# light.net
KiCad netlist of a schematic drawn in EAGLE
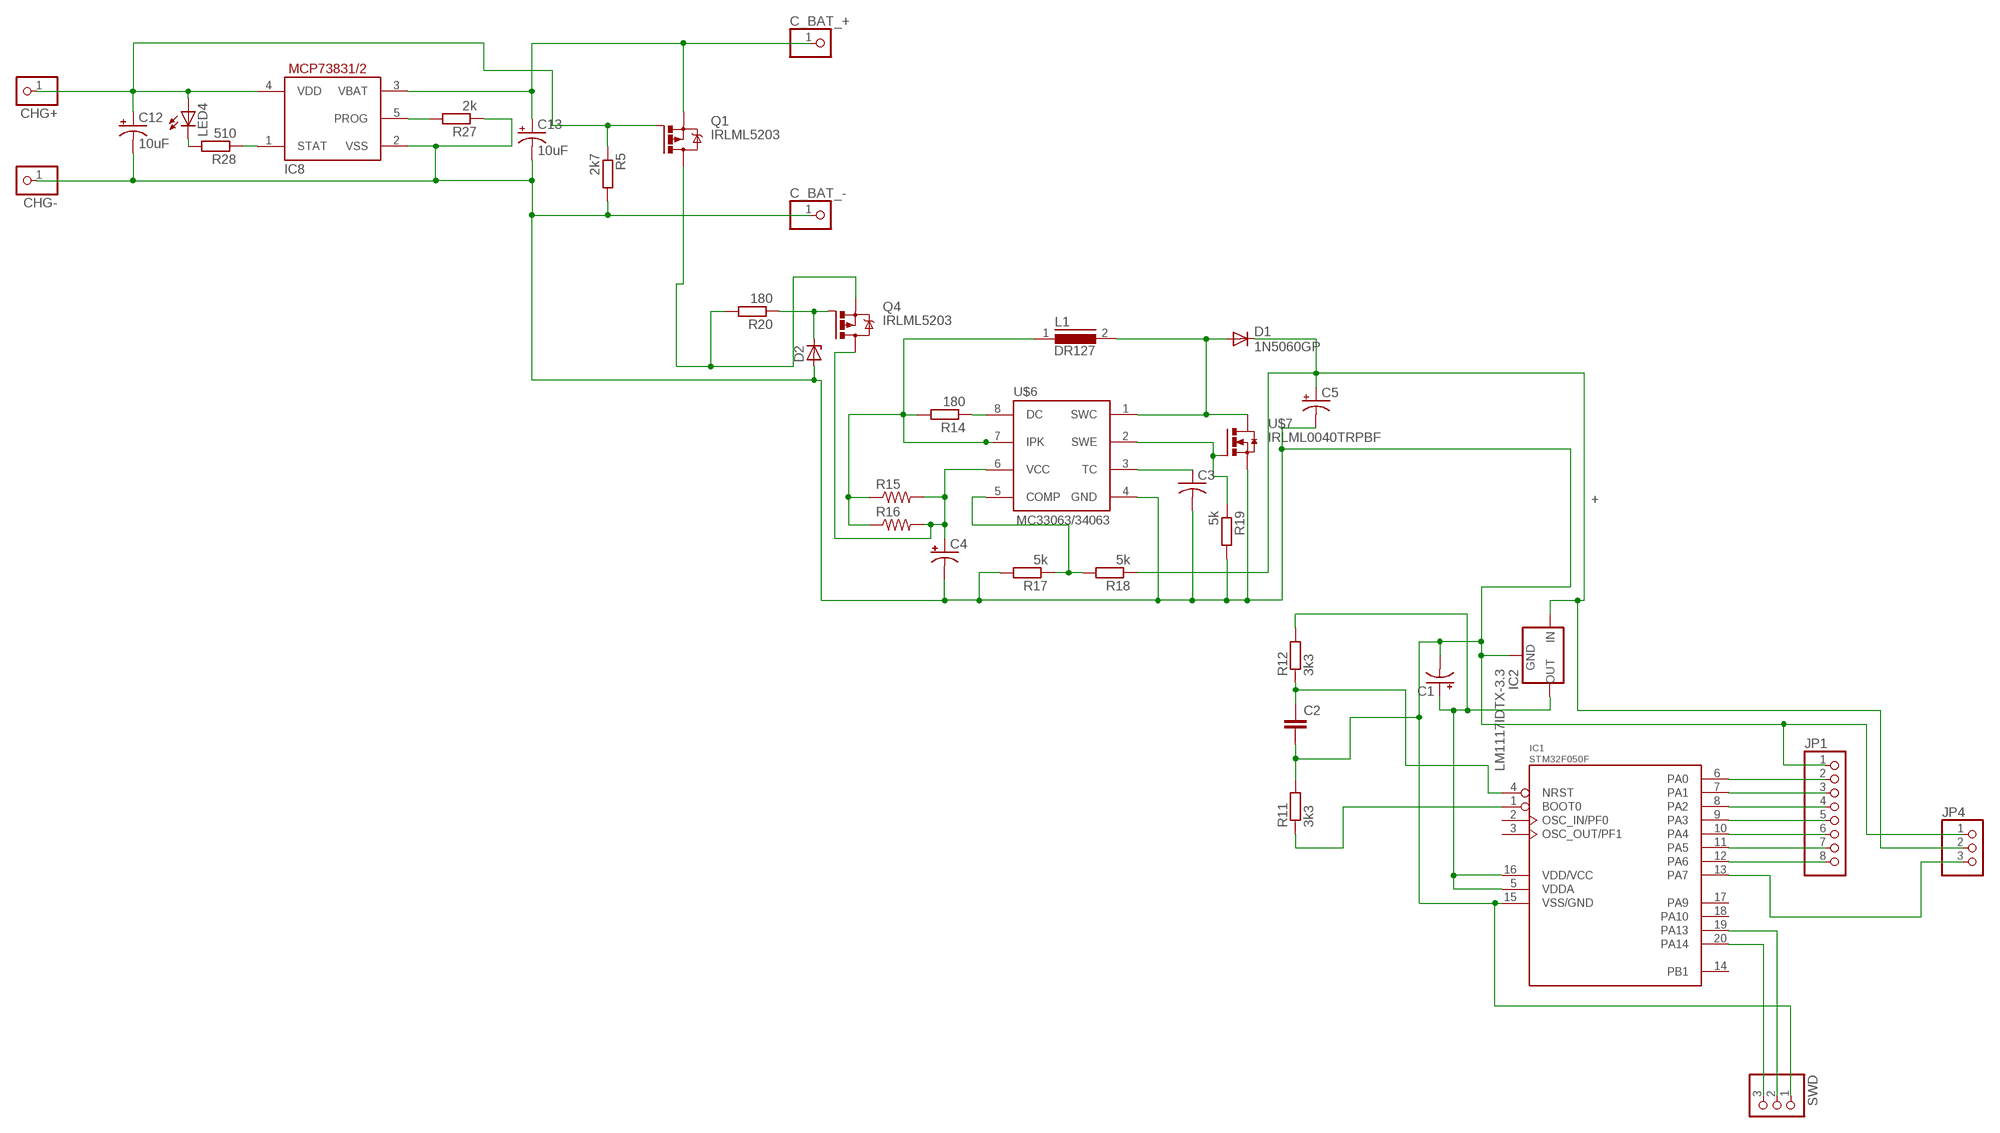
[diagram p0: schematic, sheet 1]

(export (version "E")
  (design (tool "Eeschema 10.0.6"))
  (components
    (comp (ref "C1")
      (value "CPOL-USSMCD")
      (footprint "eagle-import:SMC_D")
      (libsource (lib "eagle-import") (part "CPOL-USSMCD"))
    )
    (comp (ref "C2")
      (value "C-EUC1206")
      (footprint "eagle-import:C1206")
      (libsource (lib "eagle-import") (part "C-EUC1206"))
    )
    (comp (ref "C3")
      (value "C-US050-024X044")
      (footprint "eagle-import:C050-024X044")
      (libsource (lib "eagle-import") (part "C-US050-024X044"))
    )
    (comp (ref "C4")
      (value "CPOL-USE5-8.5")
      (footprint "eagle-import:E5-8,5")
      (libsource (lib "eagle-import") (part "CPOL-USE5-8.5"))
    )
    (comp (ref "C5")
      (value "CPOL-USE5-8.5")
      (footprint "eagle-import:E5-8,5")
      (libsource (lib "eagle-import") (part "CPOL-USE5-8.5"))
    )
    (comp (ref "C12")
      (value "10uF")
      (footprint "eagle-import:SMC_D")
      (libsource (lib "eagle-import") (part "CPOL-USSMCD"))
    )
    (comp (ref "C13")
      (value "10uF")
      (footprint "eagle-import:SMC_D")
      (libsource (lib "eagle-import") (part "CPOL-USSMCD"))
    )
    (comp (ref "CHG+")
      (value "PINHD-1X1")
      (footprint "eagle-import:1X01")
      (libsource (lib "eagle-import") (part "PINHD-1X1"))
    )
    (comp (ref "CHG-")
      (value "PINHD-1X1")
      (footprint "eagle-import:1X01")
      (libsource (lib "eagle-import") (part "PINHD-1X1"))
    )
    (comp (ref "C_BAT_+")
      (value "PINHD-1X1")
      (footprint "eagle-import:1X01")
      (libsource (lib "eagle-import") (part "PINHD-1X1"))
    )
    (comp (ref "C_BAT_-")
      (value "PINHD-1X1")
      (footprint "eagle-import:1X01")
      (libsource (lib "eagle-import") (part "PINHD-1X1"))
    )
    (comp (ref "D1")
      (value "1N5060GP")
      (footprint "eagle-import:DO15-12")
      (libsource (lib "eagle-import") (part "1N5060GP"))
    )
    (comp (ref "D2")
      (value "ZENER-DIODESOD80C")
      (footprint "eagle-import:SOD80C")
      (libsource (lib "eagle-import") (part "ZENER-DIODESOD80C"))
    )
    (comp (ref "IC1")
      (value "STM32F050F")
      (footprint "eagle-import:TSSOP20")
      (libsource (lib "eagle-import") (part "STM32F050F"))
    )
    (comp (ref "IC2")
      (value "LM1117IDTX-3.3")
      (footprint "eagle-import:TO252")
      (libsource (lib "eagle-import") (part "LM1117IDTX-3.3"))
    )
    (comp (ref "IC8")
      (value "MCP73831/OT")
      (footprint "eagle-import:SOT23-5L")
      (libsource (lib "eagle-import") (part "MCP73831/OT"))
    )
    (comp (ref "JP1")
      (value "PINHD-1X8")
      (footprint "eagle-import:1X08")
      (libsource (lib "eagle-import") (part "PINHD-1X8"))
    )
    (comp (ref "JP4")
      (value "PINHD-1X3")
      (footprint "eagle-import:1X03")
      (libsource (lib "eagle-import") (part "pinhead_PINHD-1X3"))
    )
    (comp (ref "L1")
      (value "DR127")
      (footprint "eagle-import:DR127")
      (libsource (lib "eagle-import") (part "DR127"))
    )
    (comp (ref "LED4")
      (value "LED")
      (footprint "eagle-import:SMARTLED-TTW")
      (libsource (lib "eagle-import") (part "LED"))
    )
    (comp (ref "Q1")
      (value "IRLML5203")
      (footprint "eagle-import:MICRO3")
      (libsource (lib "eagle-import") (part "IRLML5203"))
    )
    (comp (ref "Q4")
      (value "IRLML5203")
      (footprint "eagle-import:MICRO3")
      (libsource (lib "eagle-import") (part "IRLML5203"))
    )
    (comp (ref "R5")
      (value "2k7")
      (footprint "eagle-import:M1206")
      (libsource (lib "eagle-import") (part "R-EU_M1206"))
    )
    (comp (ref "R11")
      (value "3k3")
      (footprint "eagle-import:M1206")
      (libsource (lib "eagle-import") (part "R-EU_M1206"))
    )
    (comp (ref "R12")
      (value "3k3")
      (footprint "eagle-import:M1206")
      (libsource (lib "eagle-import") (part "R-EU_M1206"))
    )
    (comp (ref "R14")
      (value "180")
      (footprint "eagle-import:M1206")
      (libsource (lib "eagle-import") (part "R-EU_M1206"))
    )
    (comp (ref "R15")
      (value "R-US_0207/12")
      (footprint "eagle-import:0207_12")
      (libsource (lib "eagle-import") (part "R-US_0207/12"))
    )
    (comp (ref "R16")
      (value "R-US_0207/12")
      (footprint "eagle-import:0207_12")
      (libsource (lib "eagle-import") (part "R-US_0207/12"))
    )
    (comp (ref "R17")
      (value "5k")
      (footprint "eagle-import:M1206")
      (libsource (lib "eagle-import") (part "R-EU_M1206"))
    )
    (comp (ref "R18")
      (value "5k")
      (footprint "eagle-import:M1206")
      (libsource (lib "eagle-import") (part "R-EU_M1206"))
    )
    (comp (ref "R19")
      (value "5k")
      (footprint "eagle-import:M1206")
      (libsource (lib "eagle-import") (part "R-EU_M1206"))
    )
    (comp (ref "R20")
      (value "180")
      (footprint "eagle-import:M1206")
      (libsource (lib "eagle-import") (part "R-EU_M1206"))
    )
    (comp (ref "R27")
      (value "2k")
      (footprint "eagle-import:M1206")
      (libsource (lib "eagle-import") (part "R-EU_M1206"))
    )
    (comp (ref "R28")
      (value "510")
      (footprint "eagle-import:M1206")
      (libsource (lib "eagle-import") (part "R-EU_M1206"))
    )
    (comp (ref "SWD")
      (value "PINHD-1X3")
      (footprint "eagle-import:1X03")
      (libsource (lib "eagle-import") (part "PINHD-1X3"))
    )
    (comp (ref "U$6")
      (value "MC33063/MC34063D")
      (footprint "eagle-import:SO08")
      (libsource (lib "eagle-import") (part "MC33063/MC34063D"))
    )
    (comp (ref "U$7")
      (value "IRLML0040TRPBF")
      (footprint "eagle-import:MICRO3")
      (libsource (lib "eagle-import") (part "IRLML0040TRPBF"))
    )
  )
  (nets
    (net (code "1") (name "Net-(IC1-BOOT0)") (class "Default")
      (node (ref "IC1") (pin "1") (pinfunction "BOOT0_1") (pintype "bidirectional"))
      (node (ref "R11") (pin "1") (pinfunction "1_1") (pintype "passive"))
    )
    (net (code "2") (name "Net-(IC1-NRST)") (class "Default")
      (node (ref "C2") (pin "1") (pinfunction "1_1") (pintype "passive"))
      (node (ref "IC1") (pin "4") (pinfunction "NRST_4") (pintype "bidirectional"))
      (node (ref "R12") (pin "1") (pinfunction "1_1") (pintype "passive"))
    )
    (net (code "3") (name "Net-(IC1-PA0)") (class "Default")
      (node (ref "IC1") (pin "6") (pinfunction "PA0_6") (pintype "bidirectional"))
      (node (ref "JP1") (pin "2") (pinfunction "2_2") (pintype "passive"))
    )
    (net (code "4") (name "Net-(IC1-PA1)") (class "Default")
      (node (ref "IC1") (pin "7") (pinfunction "PA1_7") (pintype "bidirectional"))
      (node (ref "JP1") (pin "3") (pinfunction "3_3") (pintype "passive"))
    )
    (net (code "5") (name "Net-(IC1-PA2)") (class "Default")
      (node (ref "IC1") (pin "8") (pinfunction "PA2_8") (pintype "bidirectional"))
      (node (ref "JP1") (pin "4") (pinfunction "4_4") (pintype "passive"))
    )
    (net (code "6") (name "Net-(IC1-PA3)") (class "Default")
      (node (ref "IC1") (pin "9") (pinfunction "PA3_9") (pintype "bidirectional"))
      (node (ref "JP1") (pin "5") (pinfunction "5_5") (pintype "passive"))
    )
    (net (code "7") (name "Net-(IC1-PA4)") (class "Default")
      (node (ref "IC1") (pin "10") (pinfunction "PA4_10") (pintype "bidirectional"))
      (node (ref "JP1") (pin "6") (pinfunction "6_6") (pintype "passive"))
    )
    (net (code "8") (name "Net-(IC1-PA5)") (class "Default")
      (node (ref "IC1") (pin "11") (pinfunction "PA5_11") (pintype "bidirectional"))
      (node (ref "JP1") (pin "7") (pinfunction "7_7") (pintype "passive"))
    )
    (net (code "9") (name "Net-(IC1-PA6)") (class "Default")
      (node (ref "IC1") (pin "12") (pinfunction "PA6_12") (pintype "bidirectional"))
      (node (ref "JP1") (pin "8") (pinfunction "8_8") (pintype "passive"))
    )
    (net (code "10") (name "Net-(IC1-PA7)") (class "Default")
      (node (ref "IC1") (pin "13") (pinfunction "PA7_13") (pintype "bidirectional"))
      (node (ref "JP4") (pin "3") (pinfunction "3_3") (pintype "passive"))
    )
    (net (code "11") (name "Net-(IC1-PA13)") (class "Default")
      (node (ref "IC1") (pin "19") (pinfunction "PA13_19") (pintype "bidirectional"))
      (node (ref "SWD") (pin "2") (pinfunction "2_2") (pintype "passive"))
    )
    (net (code "12") (name "Net-(IC1-PA14)") (class "Default")
      (node (ref "IC1") (pin "20") (pinfunction "PA14_20") (pintype "bidirectional"))
      (node (ref "SWD") (pin "3") (pinfunction "3_3") (pintype "passive"))
    )
    (net (code "13") (name "Net-(IC1-VDDA)") (class "Default")
      (node (ref "C1") (pin "+") (pinfunction "+_+") (pintype "passive"))
      (node (ref "IC1") (pin "16") (pinfunction "VDD/VCC_16") (pintype "power_in"))
      (node (ref "IC1") (pin "5") (pinfunction "VDDA_5") (pintype "power_in"))
      (node (ref "IC2") (pin "TAB") (pinfunction "OUT_TAB") (pintype "passive"))
      (node (ref "R12") (pin "2") (pinfunction "2_2") (pintype "passive"))
    )
    (net (code "14") (name "Net-(IC1-VSS{slash}GND)") (class "Default")
      (node (ref "C1") (pin "-") (pinfunction "-_-") (pintype "passive"))
      (node (ref "C12") (pin "-") (pinfunction "-_-") (pintype "passive"))
      (node (ref "C13") (pin "-") (pinfunction "-_-") (pintype "passive"))
      (node (ref "C2") (pin "2") (pinfunction "2_2") (pintype "passive"))
      (node (ref "C3") (pin "2") (pinfunction "2_2") (pintype "passive"))
      (node (ref "C4") (pin "-") (pinfunction "-_-") (pintype "passive"))
      (node (ref "C5") (pin "-") (pinfunction "-_-") (pintype "passive"))
      (node (ref "CHG-") (pin "1") (pinfunction "1_1") (pintype "passive"))
      (node (ref "C_BAT_-") (pin "1") (pinfunction "1_1") (pintype "passive"))
      (node (ref "D2") (pin "A") (pinfunction "A_A") (pintype "passive"))
      (node (ref "IC1") (pin "15") (pinfunction "VSS/GND_15") (pintype "power_in"))
      (node (ref "IC2") (pin "1") (pinfunction "GND_1") (pintype "input"))
      (node (ref "IC8") (pin "2") (pinfunction "VSS_2") (pintype "power_in"))
      (node (ref "JP1") (pin "1") (pinfunction "1_1") (pintype "passive"))
      (node (ref "JP4") (pin "1") (pinfunction "1_1") (pintype "passive"))
      (node (ref "R11") (pin "2") (pinfunction "2_2") (pintype "passive"))
      (node (ref "R17") (pin "2") (pinfunction "2_2") (pintype "passive"))
      (node (ref "R19") (pin "2") (pinfunction "2_2") (pintype "passive"))
      (node (ref "R27") (pin "1") (pinfunction "1_1") (pintype "passive"))
      (node (ref "R5") (pin "2") (pinfunction "2_2") (pintype "passive"))
      (node (ref "SWD") (pin "1") (pinfunction "1_1") (pintype "passive"))
      (node (ref "U$6") (pin "4") (pinfunction "GND_4") (pintype "power_in"))
      (node (ref "U$7") (pin "2") (pinfunction "S_2") (pintype "passive"))
    )
    (net (code "15") (name "Net-(IC2-IN)") (class "Default")
      (node (ref "C5") (pin "+") (pinfunction "+_+") (pintype "passive"))
      (node (ref "D1") (pin "C") (pinfunction "C_C") (pintype "passive"))
      (node (ref "IC2") (pin "2") (pinfunction "IN_2") (pintype "input"))
      (node (ref "JP4") (pin "2") (pinfunction "2_2") (pintype "passive"))
      (node (ref "R18") (pin "1") (pinfunction "1_1") (pintype "passive"))
    )
    (net (code "16") (name "Net-(IC8-PROG)") (class "Default")
      (node (ref "IC8") (pin "5") (pinfunction "PROG_5") (pintype "input"))
      (node (ref "R27") (pin "2") (pinfunction "2_2") (pintype "passive"))
    )
    (net (code "17") (name "Net-(IC8-STAT)") (class "Default")
      (node (ref "IC8") (pin "1") (pinfunction "STAT_1") (pintype "output"))
      (node (ref "R28") (pin "1") (pinfunction "1_1") (pintype "passive"))
    )
    (net (code "18") (name "Net-(IC8-VBAT)") (class "Default")
      (node (ref "C13") (pin "+") (pinfunction "+_+") (pintype "passive"))
      (node (ref "C_BAT_+") (pin "1") (pinfunction "1_1") (pintype "passive"))
      (node (ref "IC8") (pin "3") (pinfunction "VBAT_3") (pintype "bidirectional"))
      (node (ref "Q1") (pin "2") (pinfunction "S_2") (pintype "passive"))
    )
    (net (code "19") (name "Net-(IC8-VDD)") (class "Default")
      (node (ref "C12") (pin "+") (pinfunction "+_+") (pintype "passive"))
      (node (ref "CHG+") (pin "1") (pinfunction "1_1") (pintype "passive"))
      (node (ref "IC8") (pin "4") (pinfunction "VDD_4") (pintype "power_in"))
      (node (ref "LED4") (pin "A@1") (pinfunction "A_A@1") (pintype "passive"))
      (node (ref "Q1") (pin "1") (pinfunction "G_1") (pintype "passive"))
      (node (ref "R5") (pin "1") (pinfunction "1_1") (pintype "passive"))
    )
    (net (code "20") (name "Net-(LED4-C)") (class "Default")
      (node (ref "LED4") (pin "C@1") (pinfunction "C_C@1") (pintype "passive"))
      (node (ref "R28") (pin "2") (pinfunction "2_2") (pintype "passive"))
    )
    (net (code "21") (name "Net-(Q1-D)") (class "Default")
      (node (ref "Q1") (pin "3") (pinfunction "D_3") (pintype "passive"))
      (node (ref "Q4") (pin "2") (pinfunction "S_2") (pintype "passive"))
      (node (ref "R20") (pin "2") (pinfunction "2_2") (pintype "passive"))
    )
    (net (code "22") (name "Net-(Q4-D)") (class "Default")
      (node (ref "C4") (pin "+") (pinfunction "+_+") (pintype "passive"))
      (node (ref "Q4") (pin "3") (pinfunction "D_3") (pintype "passive"))
      (node (ref "R15") (pin "2") (pinfunction "2_2") (pintype "passive"))
      (node (ref "R16") (pin "2") (pinfunction "2_2") (pintype "passive"))
      (node (ref "U$6") (pin "6") (pinfunction "VCC_6") (pintype "power_in"))
    )
    (net (code "23") (name "Net-(Q4-G)") (class "Default")
      (node (ref "D2") (pin "C") (pinfunction "C_C") (pintype "passive"))
      (node (ref "Q4") (pin "1") (pinfunction "G_1") (pintype "passive"))
      (node (ref "R20") (pin "1") (pinfunction "1_1") (pintype "passive"))
    )
    (net (code "24") (name "Net-(U$6-COMP)") (class "Default")
      (node (ref "R17") (pin "1") (pinfunction "1_1") (pintype "passive"))
      (node (ref "R18") (pin "2") (pinfunction "2_2") (pintype "passive"))
      (node (ref "U$6") (pin "5") (pinfunction "COMP_5") (pintype "input"))
    )
    (net (code "25") (name "Net-(U$6-DC)") (class "Default")
      (node (ref "R14") (pin "1") (pinfunction "1_1") (pintype "passive"))
      (node (ref "U$6") (pin "8") (pinfunction "DC_8") (pintype "input"))
    )
    (net (code "26") (name "Net-(U$6-IPK)") (class "Default")
      (node (ref "L1") (pin "1") (pinfunction "1_1") (pintype "passive"))
      (node (ref "R14") (pin "2") (pinfunction "2_2") (pintype "passive"))
      (node (ref "R15") (pin "1") (pinfunction "1_1") (pintype "passive"))
      (node (ref "R16") (pin "1") (pinfunction "1_1") (pintype "passive"))
      (node (ref "U$6") (pin "7") (pinfunction "IPK_7") (pintype "bidirectional"))
    )
    (net (code "27") (name "Net-(U$6-SWC)") (class "Default")
      (node (ref "D1") (pin "A") (pinfunction "A_A") (pintype "passive"))
      (node (ref "L1") (pin "2") (pinfunction "2_2") (pintype "passive"))
      (node (ref "U$6") (pin "1") (pinfunction "SWC_1") (pintype "input"))
      (node (ref "U$7") (pin "3") (pinfunction "D_3") (pintype "passive"))
    )
    (net (code "28") (name "Net-(U$6-SWE)") (class "Default")
      (node (ref "R19") (pin "1") (pinfunction "1_1") (pintype "passive"))
      (node (ref "U$6") (pin "2") (pinfunction "SWE_2") (pintype "input"))
      (node (ref "U$7") (pin "1") (pinfunction "G_1") (pintype "passive"))
    )
    (net (code "29") (name "Net-(U$6-TC)") (class "Default")
      (node (ref "C3") (pin "1") (pinfunction "1_1") (pintype "passive"))
      (node (ref "U$6") (pin "3") (pinfunction "TC_3") (pintype "input"))
    )
    (net (code "30") (name "unconnected-(IC1-OSC_IN{slash}PF0-Pad2)") (class "Default")
      (node (ref "IC1") (pin "2") (pinfunction "OSC_IN/PF0_2") (pintype "bidirectional"))
    )
    (net (code "31") (name "unconnected-(IC1-OSC_OUT{slash}PF1-Pad3)") (class "Default")
      (node (ref "IC1") (pin "3") (pinfunction "OSC_OUT/PF1_3") (pintype "bidirectional"))
    )
    (net (code "32") (name "unconnected-(IC1-PA9-Pad17)") (class "Default")
      (node (ref "IC1") (pin "17") (pinfunction "PA9_17") (pintype "bidirectional"))
    )
    (net (code "33") (name "unconnected-(IC1-PA10-Pad18)") (class "Default")
      (node (ref "IC1") (pin "18") (pinfunction "PA10_18") (pintype "bidirectional"))
    )
    (net (code "34") (name "unconnected-(IC1-PB1-Pad14)") (class "Default")
      (node (ref "IC1") (pin "14") (pinfunction "PB1_14") (pintype "bidirectional"))
    )
  )
)
